# MCU_Platform.net
KiCad netlist of a schematic drawn in Altium Designer
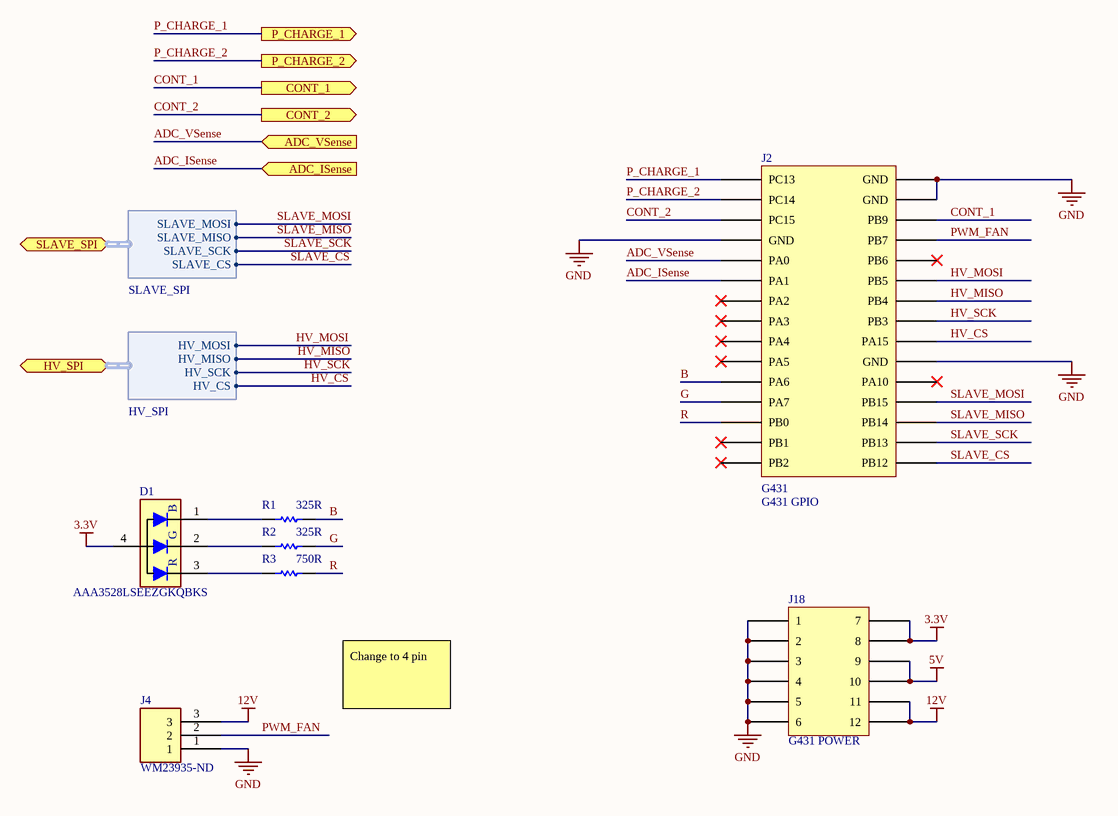
[diagram p0: MCU_Platform.SchDoc]

(export (version "E")
  (design (tool "Eeschema 10.0.6"))
  (components
    (comp (ref "D1")
      (value "AAA3528LSEEZGKQBKS")
      (footprint "4-PLCC RGB LED")
      (fields (field (name "MANUFACTURER") "Kingbright"))
      (libsource (lib "General") (part "RGB LED- Common Anode"))
    )
    (comp (ref "J2")
      (value "G431 GPIO")
      (footprint "G431 Header (GPIO Connector)")
      (description "PPPC152LJBN-RC (30 Position Header Connector 0.100\" (2.54mm) Through Hole, Right Angle Gold)")
      (libsource (lib "MCUBoards") (part "G431 GPIO"))
    )
    (comp (ref "J4")
      (value "WM23935-ND")
      (footprint "MOLEX_39303037")
      (description "Conn Power HDR 3 POS 4.2mm Solder RA Thru-Hole 3 Terminal 1 Port Mini-Fit Jr Bag")
      (fields (field (name "MP") "39303037") (field (name "MF") "Molex"))
      (libsource (lib "GeneralConnectors") (part "WM23935-ND"))
    )
    (comp (ref "J18")
      (value "G431 POWER")
      (footprint "G431 HEADER (POWER CONNECTOR)")
      (description "PPPC062LJBN-RC (12 Position Header Connector 0.100\" (2.54mm) Through Hole, Right Angle Gold)")
      (fields (field (name "MANUFACTURER PART NUMBER") "PPPC062LJBN-RC"))
      (libsource (lib "MCUBoards") (part "G431 POWER"))
    )
    (comp (ref "R1")
      (value "325R")
      (footprint "0603 - Resistor")
      (description "RC0603FR-07232RL, RES 232 OHM 1% 1/10W 0603")
      (fields
        (field (name "MANUFACTURER PART NUMBER") "RC0603FR-07232RL")
        (field (name "MANUFACTURER") "YAGEO")
      )
      (libsource (lib "General") (part "Resistor"))
    )
    (comp (ref "R2")
      (value "325R")
      (footprint "0603 - Resistor")
      (description "RC0603FR-07232RL, RES 232 OHM 1% 1/10W 0603")
      (fields
        (field (name "MANUFACTURER PART NUMBER") "RC0603FR-07232RL")
        (field (name "MANUFACTURER") "YAGEO")
      )
      (libsource (lib "General") (part "Resistor"))
    )
    (comp (ref "R3")
      (value "750R")
      (footprint "0603 - Resistor")
      (description "RC0603FR-07232RL, RES 232 OHM 1% 1/10W 0603")
      (fields
        (field (name "MANUFACTURER PART NUMBER") "RC0603FR-07232RL")
        (field (name "MANUFACTURER") "YAGEO")
      )
      (libsource (lib "General") (part "Resistor"))
    )
  )
  (nets
    (net (code "3") (name "/ADC_ISense") (class "Default")
      (node (ref "J2") (pin "6") (pinfunction "PA1_6") (pintype "passive"))
    )
    (net (code "4") (name "/ADC_VSense") (class "Default")
      (node (ref "J2") (pin "5") (pinfunction "PA0_5") (pintype "passive"))
    )
    (net (code "5") (name "/B") (class "Default")
      (node (ref "J2") (pin "11") (pinfunction "PA6_11") (pintype "passive"))
      (node (ref "R1") (pin "1") (pinfunction "1_1") (pintype "passive"))
    )
    (net (code "6") (name "/CONT_1") (class "Default")
      (node (ref "J2") (pin "18") (pinfunction "PB9_18") (pintype "passive"))
    )
    (net (code "7") (name "/CONT_2") (class "Default")
      (node (ref "J2") (pin "3") (pinfunction "PC15_3") (pintype "passive"))
    )
    (net (code "8") (name "/G") (class "Default")
      (node (ref "J2") (pin "12") (pinfunction "PA7_12") (pintype "passive"))
      (node (ref "R2") (pin "1") (pinfunction "1_1") (pintype "passive"))
    )
    (net (code "9") (name "/HV_CS") (class "Default")
      (node (ref "J2") (pin "24") (pinfunction "PA15_24") (pintype "passive"))
    )
    (net (code "10") (name "/HV_MISO") (class "Default")
      (node (ref "J2") (pin "22") (pinfunction "PB4_22") (pintype "passive"))
    )
    (net (code "11") (name "/HV_MOSI") (class "Default")
      (node (ref "J2") (pin "21") (pinfunction "PB5_21") (pintype "passive"))
    )
    (net (code "12") (name "/HV_SCK") (class "Default")
      (node (ref "J2") (pin "23") (pinfunction "PB3_23") (pintype "passive"))
    )
    (net (code "13") (name "/PWM_FAN") (class "Default")
      (node (ref "J2") (pin "19") (pinfunction "PB7_19") (pintype "passive"))
      (node (ref "J4") (pin "2") (pinfunction "2_2") (pintype "passive"))
    )
    (net (code "14") (name "/P_CHARGE_1") (class "Default")
      (node (ref "J2") (pin "1") (pinfunction "PC13_1") (pintype "passive"))
    )
    (net (code "15") (name "/P_CHARGE_2") (class "Default")
      (node (ref "J2") (pin "2") (pinfunction "PC14_2") (pintype "passive"))
    )
    (net (code "16") (name "/R") (class "Default")
      (node (ref "J2") (pin "13") (pinfunction "PB0_13") (pintype "passive"))
      (node (ref "R3") (pin "1") (pinfunction "1_1") (pintype "passive"))
    )
    (net (code "17") (name "/SLAVE_CS") (class "Default")
      (node (ref "J2") (pin "30") (pinfunction "PB12_30") (pintype "passive"))
    )
    (net (code "18") (name "/SLAVE_MISO") (class "Default")
      (node (ref "J2") (pin "28") (pinfunction "PB14_28") (pintype "passive"))
    )
    (net (code "19") (name "/SLAVE_MOSI") (class "Default")
      (node (ref "J2") (pin "27") (pinfunction "PB15_27") (pintype "passive"))
    )
    (net (code "20") (name "/SLAVE_SCK") (class "Default")
      (node (ref "J2") (pin "29") (pinfunction "PB13_29") (pintype "passive"))
    )
    (net (code "23") (name "3.3V") (class "Default")
      (node (ref "D1") (pin "4") (pinfunction "11_4") (pintype "passive"))
      (node (ref "J18") (pin "7") (pinfunction "7_7") (pintype "passive"))
      (node (ref "J18") (pin "8") (pinfunction "8_8") (pintype "passive"))
    )
    (net (code "24") (name "5V") (class "Default")
      (node (ref "J18") (pin "10") (pinfunction "10_10") (pintype "passive"))
      (node (ref "J18") (pin "9") (pinfunction "9_9") (pintype "passive"))
    )
    (net (code "25") (name "12V") (class "Default")
      (node (ref "J18") (pin "11") (pinfunction "11_11") (pintype "passive"))
      (node (ref "J18") (pin "12") (pinfunction "12_12") (pintype "passive"))
      (node (ref "J4") (pin "3") (pinfunction "3_3") (pintype "passive"))
    )
    (net (code "26") (name "GND") (class "Default")
      (node (ref "J18") (pin "1") (pinfunction "1_1") (pintype "passive"))
      (node (ref "J18") (pin "2") (pinfunction "2_2") (pintype "passive"))
      (node (ref "J18") (pin "3") (pinfunction "3_3") (pintype "passive"))
      (node (ref "J18") (pin "4") (pinfunction "4_4") (pintype "passive"))
      (node (ref "J18") (pin "5") (pinfunction "5_5") (pintype "passive"))
      (node (ref "J18") (pin "6") (pinfunction "6_6") (pintype "passive"))
      (node (ref "J2") (pin "16") (pinfunction "GND_16") (pintype "passive"))
      (node (ref "J2") (pin "17") (pinfunction "GND_17") (pintype "passive"))
      (node (ref "J2") (pin "25") (pinfunction "GND_25") (pintype "passive"))
      (node (ref "J2") (pin "4") (pinfunction "GND_4") (pintype "passive"))
      (node (ref "J4") (pin "1") (pinfunction "1_1") (pintype "passive"))
    )
    (net (code "27") (name "Net-(D1-11-Pad1)") (class "Default")
      (node (ref "D1") (pin "1") (pinfunction "11_1") (pintype "passive"))
      (node (ref "R1") (pin "2") (pinfunction "2_2") (pintype "passive"))
    )
    (net (code "28") (name "Net-(D1-11-Pad2)") (class "Default")
      (node (ref "D1") (pin "2") (pinfunction "11_2") (pintype "passive"))
      (node (ref "R2") (pin "2") (pinfunction "2_2") (pintype "passive"))
    )
    (net (code "29") (name "Net-(D1-11-Pad3)") (class "Default")
      (node (ref "D1") (pin "3") (pinfunction "11_3") (pintype "passive"))
      (node (ref "R3") (pin "2") (pinfunction "2_2") (pintype "passive"))
    )
    (net (code "30") (name "unconnected-(J2-PA2-Pad7)") (class "Default")
      (node (ref "J2") (pin "7") (pinfunction "PA2_7") (pintype "passive+no_connect"))
    )
    (net (code "31") (name "unconnected-(J2-PA3-Pad8)") (class "Default")
      (node (ref "J2") (pin "8") (pinfunction "PA3_8") (pintype "passive+no_connect"))
    )
    (net (code "32") (name "unconnected-(J2-PA4-Pad9)") (class "Default")
      (node (ref "J2") (pin "9") (pinfunction "PA4_9") (pintype "passive+no_connect"))
    )
    (net (code "33") (name "unconnected-(J2-PA5-Pad10)") (class "Default")
      (node (ref "J2") (pin "10") (pinfunction "PA5_10") (pintype "passive+no_connect"))
    )
    (net (code "34") (name "unconnected-(J2-PA10-Pad26)") (class "Default")
      (node (ref "J2") (pin "26") (pinfunction "PA10_26") (pintype "passive+no_connect"))
    )
    (net (code "35") (name "unconnected-(J2-PB1-Pad14)") (class "Default")
      (node (ref "J2") (pin "14") (pinfunction "PB1_14") (pintype "passive+no_connect"))
    )
    (net (code "36") (name "unconnected-(J2-PB2-Pad15)") (class "Default")
      (node (ref "J2") (pin "15") (pinfunction "PB2_15") (pintype "passive+no_connect"))
    )
    (net (code "37") (name "unconnected-(J2-PB6-Pad20)") (class "Default")
      (node (ref "J2") (pin "20") (pinfunction "PB6_20") (pintype "passive+no_connect"))
    )
  )
)
